# MCU.net
KiCad netlist of a schematic drawn in Altium Designer
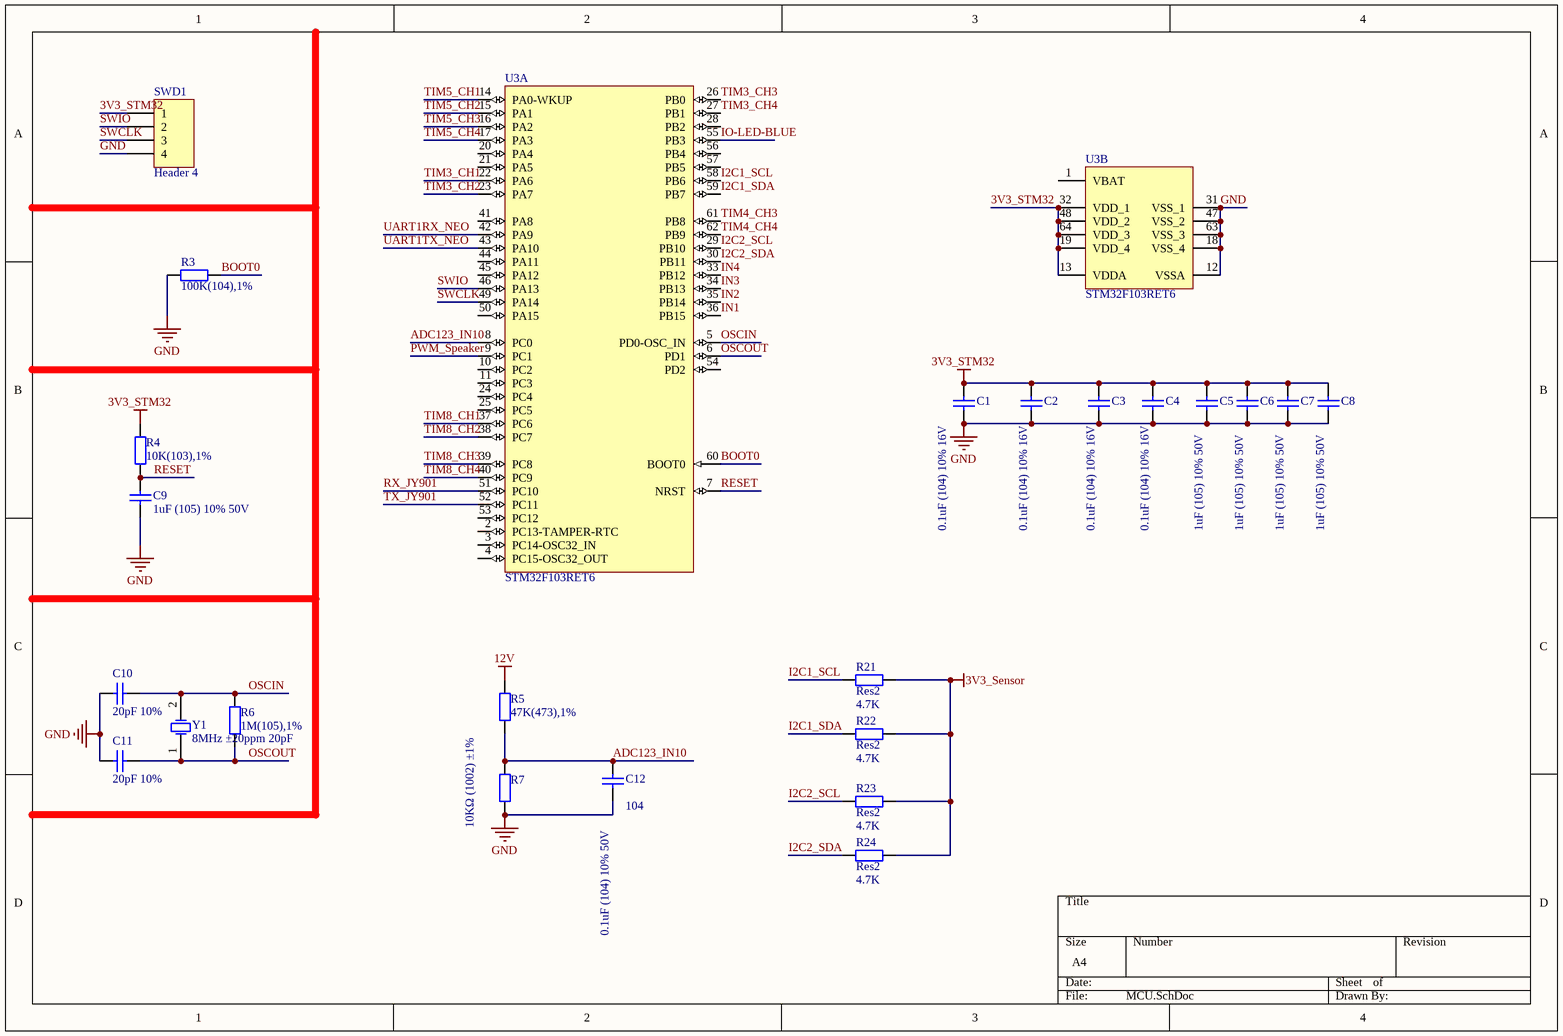
[diagram p0: MCU.SchDoc]

(export (version "E")
  (design (tool "Eeschema 10.0.6"))
  (components
    (comp (ref "C1")
      (value "0.1uF (104) 10% 16V")
      (footprint "0603_C")
      (description "Capacitor")
      (fields (field (name "PUBLISHER") "Altium Limited"))
      (libsource (lib "STM32F103C8T6(原理图库)") (part "Cap"))
    )
    (comp (ref "C2")
      (value "0.1uF (104) 10% 16V")
      (footprint "0603_C")
      (description "Capacitor")
      (fields (field (name "PUBLISHER") "Altium Limited"))
      (libsource (lib "STM32F103C8T6(原理图库)") (part "Cap"))
    )
    (comp (ref "C3")
      (value "0.1uF (104) 10% 16V")
      (footprint "0603_C")
      (description "Capacitor")
      (fields (field (name "PUBLISHER") "Altium Limited"))
      (libsource (lib "STM32F103C8T6(原理图库)") (part "Cap"))
    )
    (comp (ref "C4")
      (value "0.1uF (104) 10% 16V")
      (footprint "0603_C")
      (description "Capacitor")
      (fields (field (name "PUBLISHER") "Altium Limited"))
      (libsource (lib "STM32F103C8T6(原理图库)") (part "Cap"))
    )
    (comp (ref "C5")
      (value "1uF (105) 10% 50V")
      (footprint "0603_C")
      (description "贴片电容")
      (libsource (lib "Miscellaneous Devices LC") (part "0603 1uF (105) 10% 50V"))
    )
    (comp (ref "C6")
      (value "1uF (105) 10% 50V")
      (footprint "0603_C")
      (description "贴片电容")
      (libsource (lib "Miscellaneous Devices LC") (part "0603 1uF (105) 10% 50V"))
    )
    (comp (ref "C7")
      (value "1uF (105) 10% 50V")
      (footprint "0603_C")
      (description "贴片电容")
      (libsource (lib "Miscellaneous Devices LC") (part "0603 1uF (105) 10% 50V"))
    )
    (comp (ref "C8")
      (value "1uF (105) 10% 50V")
      (footprint "0603_C")
      (description "贴片电容")
      (libsource (lib "Miscellaneous Devices LC") (part "0603 1uF (105) 10% 50V"))
    )
    (comp (ref "C9")
      (value "1uF (105) 10% 50V")
      (footprint "0603_C")
      (description "Capacitor")
      (fields (field (name "PUBLISHER") "Altium Limited"))
      (libsource (lib "STM32F103C8T6(原理图库)") (part "Cap"))
    )
    (comp (ref "C10")
      (value "20pF 10%")
      (footprint "0603_C")
      (description "Capacitor")
      (fields (field (name "PUBLISHER") "Altium Limited"))
      (libsource (lib "STM32F103C8T6(原理图库)") (part "Cap"))
    )
    (comp (ref "C11")
      (value "20pF 10%")
      (footprint "0603_C")
      (description "Capacitor")
      (fields (field (name "PUBLISHER") "Altium Limited"))
      (libsource (lib "STM32F103C8T6(原理图库)") (part "Cap"))
    )
    (comp (ref "C12")
      (value "0.1uF (104) 10% 50V")
      (footprint "0603_C")
      (description "Capacitor")
      (fields (field (name "ALTIUM_VALUE") "104") (field (name "PUBLISHER") "Altium Limited"))
      (libsource (lib "Miscellaneous Devices") (part "Cap"))
    )
    (comp (ref "R3")
      (value "100K(104),1%")
      (footprint "0603_R")
      (description "Resistor")
      (fields (field (name "PUBLISHER") "Altium Limited"))
      (libsource (lib "") (part "Res2_1"))
    )
    (comp (ref "R4")
      (value "10K(103),1%")
      (footprint "0603_R")
      (description "Resistor")
      (fields (field (name "PUBLISHER") "Altium Limited"))
      (libsource (lib "STM32F103C8T6(原理图库)") (part "Res2"))
    )
    (comp (ref "R5")
      (value "47K(473),1%")
      (footprint "0603_R")
      (description "Resistor")
      (fields (field (name "PUBLISHER") "Altium Limited"))
      (libsource (lib "STM32F103C8T6(原理图库)") (part "Res2"))
    )
    (comp (ref "R6")
      (value "1M(105),1%")
      (footprint "0603_R")
      (description "Resistor")
      (fields (field (name "PUBLISHER") "Altium Limited"))
      (libsource (lib "STM32F103C8T6(原理图库)") (part "Res2"))
    )
    (comp (ref "R7")
      (value "10KΩ (1002) ±1%")
      (footprint "0603_R")
      (description "贴片电阻")
      (libsource (lib "Miscellaneous Devices LC") (part "0603 10KΩ (1002) 1%"))
    )
    (comp (ref "R21")
      (value "Res2")
      (footprint "R0603")
      (description "Resistor")
      (fields (field (name "ALTIUM_VALUE") "4.7K") (field (name "PUBLISHER") "Altium Limited"))
      (libsource (lib "Miscellaneous Devices") (part "Res2"))
    )
    (comp (ref "R22")
      (value "Res2")
      (footprint "R0603")
      (description "Resistor")
      (fields (field (name "ALTIUM_VALUE") "4.7K") (field (name "PUBLISHER") "Altium Limited"))
      (libsource (lib "Miscellaneous Devices") (part "Res2"))
    )
    (comp (ref "R23")
      (value "Res2")
      (footprint "R0603")
      (description "Resistor")
      (fields (field (name "ALTIUM_VALUE") "4.7K") (field (name "PUBLISHER") "Altium Limited"))
      (libsource (lib "Miscellaneous Devices") (part "Res2"))
    )
    (comp (ref "R24")
      (value "Res2")
      (footprint "R0603")
      (description "Resistor")
      (fields (field (name "ALTIUM_VALUE") "4.7K") (field (name "PUBLISHER") "Altium Limited"))
      (libsource (lib "Miscellaneous Devices") (part "Res2"))
    )
    (comp (ref "SWD1")
      (value "Header 4")
      (footprint "HDR1X4")
      (description "Header, 4-Pin")
      (fields (field (name "PUBLISHER") "Altium Limited"))
      (libsource (lib "Miscellaneous Connectors") (part "Header 4"))
    )
    (comp (ref "U3")
      (value "STM32F103RET6")
      (footprint "LQFP-64_10x10x05P")
      (description "ARM")
      (libsource (lib "Miscellaneous Devices LC") (part "STM32F103RET6"))
    )
    (comp (ref "Y1")
      (value "8MHz ±20ppm 20pF")
      (footprint "SMD-5032_2P")
      (description "贴片晶振")
      (libsource (lib "Miscellaneous Devices LC") (part "SMD-5032_2P 8MHz 20ppm 20pF"))
    )
  )
  (nets
    (net (code "1") (name "/ADC123_IN10") (class "Default")
      (node (ref "C12") (pin "2") (pinfunction "2_2") (pintype "passive"))
      (node (ref "R5") (pin "1") (pinfunction "1_1") (pintype "passive"))
      (node (ref "R7") (pin "2") (pinfunction "2_2") (pintype "passive"))
      (node (ref "U3") (pin "8") (pinfunction "PC0_8") (pintype "bidirectional"))
    )
    (net (code "2") (name "/BOOT0") (class "Default")
      (node (ref "R3") (pin "2") (pinfunction "2_2") (pintype "passive"))
      (node (ref "U3") (pin "60") (pinfunction "BOOT0_60") (pintype "input"))
    )
    (net (code "3") (name "/I2C1_SCL") (class "Default")
      (node (ref "R21") (pin "1") (pinfunction "1_1") (pintype "passive"))
      (node (ref "U3") (pin "58") (pinfunction "PB6_58") (pintype "bidirectional"))
    )
    (net (code "4") (name "/I2C1_SDA") (class "Default")
      (node (ref "R22") (pin "1") (pinfunction "1_1") (pintype "passive"))
      (node (ref "U3") (pin "59") (pinfunction "PB7_59") (pintype "bidirectional"))
    )
    (net (code "5") (name "/I2C2_SCL") (class "Default")
      (node (ref "R23") (pin "1") (pinfunction "1_1") (pintype "passive"))
      (node (ref "U3") (pin "29") (pinfunction "PB10_29") (pintype "bidirectional"))
    )
    (net (code "6") (name "/I2C2_SDA") (class "Default")
      (node (ref "R24") (pin "1") (pinfunction "1_1") (pintype "passive"))
      (node (ref "U3") (pin "30") (pinfunction "PB11_30") (pintype "bidirectional"))
    )
    (net (code "7") (name "/IN1") (class "Default")
      (node (ref "U3") (pin "36") (pinfunction "PB15_36") (pintype "bidirectional"))
    )
    (net (code "8") (name "/IN2") (class "Default")
      (node (ref "U3") (pin "35") (pinfunction "PB14_35") (pintype "bidirectional"))
    )
    (net (code "9") (name "/IN3") (class "Default")
      (node (ref "U3") (pin "34") (pinfunction "PB13_34") (pintype "bidirectional"))
    )
    (net (code "10") (name "/IN4") (class "Default")
      (node (ref "U3") (pin "33") (pinfunction "PB12_33") (pintype "bidirectional"))
    )
    (net (code "11") (name "/IO-LED-BLUE") (class "Default")
      (node (ref "U3") (pin "55") (pinfunction "PB3_55") (pintype "bidirectional"))
    )
    (net (code "12") (name "/OSCIN") (class "Default")
      (node (ref "C10") (pin "1") (pinfunction "1_1") (pintype "passive"))
      (node (ref "R6") (pin "2") (pinfunction "2_2") (pintype "passive"))
      (node (ref "U3") (pin "5") (pinfunction "PD0-OSC_IN_5") (pintype "bidirectional"))
      (node (ref "Y1") (pin "2") (pinfunction "OSC2_2") (pintype "passive"))
    )
    (net (code "13") (name "/OSCOUT") (class "Default")
      (node (ref "C11") (pin "1") (pinfunction "1_1") (pintype "passive"))
      (node (ref "R6") (pin "1") (pinfunction "1_1") (pintype "passive"))
      (node (ref "U3") (pin "6") (pinfunction "PD1_6") (pintype "bidirectional"))
      (node (ref "Y1") (pin "1") (pinfunction "OSC1_1") (pintype "passive"))
    )
    (net (code "14") (name "/PWM_Speaker") (class "Default")
      (node (ref "U3") (pin "9") (pinfunction "PC1_9") (pintype "bidirectional"))
    )
    (net (code "15") (name "/RESET") (class "Default")
      (node (ref "C9") (pin "2") (pinfunction "2_2") (pintype "passive"))
      (node (ref "R4") (pin "1") (pinfunction "1_1") (pintype "passive"))
      (node (ref "U3") (pin "7") (pinfunction "NRST_7") (pintype "bidirectional"))
    )
    (net (code "16") (name "/RX_JY901") (class "Default")
      (node (ref "U3") (pin "51") (pinfunction "PC10_51") (pintype "bidirectional"))
    )
    (net (code "17") (name "/SWCLK") (class "Default")
      (node (ref "SWD1") (pin "3") (pinfunction "3_3") (pintype "passive"))
      (node (ref "U3") (pin "49") (pinfunction "PA14_49") (pintype "bidirectional"))
    )
    (net (code "18") (name "/SWIO") (class "Default")
      (node (ref "SWD1") (pin "2") (pinfunction "2_2") (pintype "passive"))
      (node (ref "U3") (pin "46") (pinfunction "PA13_46") (pintype "bidirectional"))
    )
    (net (code "19") (name "/TIM3_CH1") (class "Default")
      (node (ref "U3") (pin "22") (pinfunction "PA6_22") (pintype "bidirectional"))
    )
    (net (code "20") (name "/TIM3_CH2") (class "Default")
      (node (ref "U3") (pin "23") (pinfunction "PA7_23") (pintype "bidirectional"))
    )
    (net (code "21") (name "/TIM3_CH3") (class "Default")
      (node (ref "U3") (pin "26") (pinfunction "PB0_26") (pintype "bidirectional"))
    )
    (net (code "22") (name "/TIM3_CH4") (class "Default")
      (node (ref "U3") (pin "27") (pinfunction "PB1_27") (pintype "bidirectional"))
    )
    (net (code "23") (name "/TIM4_CH3") (class "Default")
      (node (ref "U3") (pin "61") (pinfunction "PB8_61") (pintype "bidirectional"))
    )
    (net (code "24") (name "/TIM4_CH4") (class "Default")
      (node (ref "U3") (pin "62") (pinfunction "PB9_62") (pintype "bidirectional"))
    )
    (net (code "25") (name "/TIM5_CH1") (class "Default")
      (node (ref "U3") (pin "14") (pinfunction "PA0-WKUP_14") (pintype "bidirectional"))
    )
    (net (code "26") (name "/TIM5_CH2") (class "Default")
      (node (ref "U3") (pin "15") (pinfunction "PA1_15") (pintype "bidirectional"))
    )
    (net (code "27") (name "/TIM5_CH3") (class "Default")
      (node (ref "U3") (pin "16") (pinfunction "PA2_16") (pintype "bidirectional"))
    )
    (net (code "28") (name "/TIM5_CH4") (class "Default")
      (node (ref "U3") (pin "17") (pinfunction "PA3_17") (pintype "bidirectional"))
    )
    (net (code "29") (name "/TIM8_CH1") (class "Default")
      (node (ref "U3") (pin "37") (pinfunction "PC6_37") (pintype "bidirectional"))
    )
    (net (code "30") (name "/TIM8_CH2") (class "Default")
      (node (ref "U3") (pin "38") (pinfunction "PC7_38") (pintype "bidirectional"))
    )
    (net (code "31") (name "/TIM8_CH3") (class "Default")
      (node (ref "U3") (pin "39") (pinfunction "PC8_39") (pintype "bidirectional"))
    )
    (net (code "32") (name "/TIM8_CH4") (class "Default")
      (node (ref "U3") (pin "40") (pinfunction "PC9_40") (pintype "bidirectional"))
    )
    (net (code "33") (name "/TX_JY901") (class "Default")
      (node (ref "U3") (pin "52") (pinfunction "PC11_52") (pintype "bidirectional"))
    )
    (net (code "34") (name "/UART1RX_NEO") (class "Default")
      (node (ref "U3") (pin "42") (pinfunction "PA9_42") (pintype "bidirectional"))
    )
    (net (code "35") (name "/UART1TX_NEO") (class "Default")
      (node (ref "U3") (pin "43") (pinfunction "PA10_43") (pintype "bidirectional"))
    )
    (net (code "36") (name "3V3_STM32") (class "Default")
      (node (ref "C1") (pin "2") (pinfunction "2_2") (pintype "passive"))
      (node (ref "C2") (pin "2") (pinfunction "2_2") (pintype "passive"))
      (node (ref "C3") (pin "2") (pinfunction "2_2") (pintype "passive"))
      (node (ref "C4") (pin "2") (pinfunction "2_2") (pintype "passive"))
      (node (ref "C5") (pin "2") (pinfunction "2_2") (pintype "passive"))
      (node (ref "C6") (pin "2") (pinfunction "2_2") (pintype "passive"))
      (node (ref "C7") (pin "2") (pinfunction "2_2") (pintype "passive"))
      (node (ref "C8") (pin "2") (pinfunction "2_2") (pintype "passive"))
      (node (ref "R4") (pin "2") (pinfunction "2_2") (pintype "passive"))
      (node (ref "SWD1") (pin "1") (pinfunction "1_1") (pintype "passive"))
      (node (ref "U3") (pin "13") (pinfunction "VDDA_13") (pintype "power_in"))
      (node (ref "U3") (pin "19") (pinfunction "VDD_4_19") (pintype "power_in"))
      (node (ref "U3") (pin "32") (pinfunction "VDD_1_32") (pintype "power_in"))
      (node (ref "U3") (pin "48") (pinfunction "VDD_2_48") (pintype "power_in"))
      (node (ref "U3") (pin "64") (pinfunction "VDD_3_64") (pintype "power_in"))
    )
    (net (code "37") (name "3V3_Sensor") (class "Default")
      (node (ref "R21") (pin "2") (pinfunction "2_2") (pintype "passive"))
      (node (ref "R22") (pin "2") (pinfunction "2_2") (pintype "passive"))
      (node (ref "R23") (pin "2") (pinfunction "2_2") (pintype "passive"))
      (node (ref "R24") (pin "2") (pinfunction "2_2") (pintype "passive"))
    )
    (net (code "38") (name "12V") (class "Default")
      (node (ref "R5") (pin "2") (pinfunction "2_2") (pintype "passive"))
    )
    (net (code "39") (name "GND") (class "Default")
      (node (ref "C1") (pin "1") (pinfunction "1_1") (pintype "passive"))
      (node (ref "C10") (pin "2") (pinfunction "2_2") (pintype "passive"))
      (node (ref "C11") (pin "2") (pinfunction "2_2") (pintype "passive"))
      (node (ref "C12") (pin "1") (pinfunction "1_1") (pintype "passive"))
      (node (ref "C2") (pin "1") (pinfunction "1_1") (pintype "passive"))
      (node (ref "C3") (pin "1") (pinfunction "1_1") (pintype "passive"))
      (node (ref "C4") (pin "1") (pinfunction "1_1") (pintype "passive"))
      (node (ref "C5") (pin "1") (pinfunction "1_1") (pintype "passive"))
      (node (ref "C6") (pin "1") (pinfunction "1_1") (pintype "passive"))
      (node (ref "C7") (pin "1") (pinfunction "1_1") (pintype "passive"))
      (node (ref "C8") (pin "1") (pinfunction "1_1") (pintype "passive"))
      (node (ref "C9") (pin "1") (pinfunction "1_1") (pintype "passive"))
      (node (ref "R3") (pin "1") (pinfunction "1_1") (pintype "passive"))
      (node (ref "R7") (pin "1") (pinfunction "1_1") (pintype "passive"))
      (node (ref "SWD1") (pin "4") (pinfunction "4_4") (pintype "passive"))
      (node (ref "U3") (pin "12") (pinfunction "VSSA_12") (pintype "power_in"))
      (node (ref "U3") (pin "18") (pinfunction "VSS_4_18") (pintype "power_in"))
      (node (ref "U3") (pin "31") (pinfunction "VSS_1_31") (pintype "power_in"))
      (node (ref "U3") (pin "47") (pinfunction "VSS_2_47") (pintype "power_in"))
      (node (ref "U3") (pin "63") (pinfunction "VSS_3_63") (pintype "power_in"))
    )
    (net (code "40") (name "unconnected-(U3A-PA4-Pad20)") (class "Default")
      (node (ref "U3") (pin "20") (pinfunction "PA4_20") (pintype "bidirectional"))
    )
    (net (code "41") (name "unconnected-(U3A-PA5-Pad21)") (class "Default")
      (node (ref "U3") (pin "21") (pinfunction "PA5_21") (pintype "bidirectional"))
    )
    (net (code "42") (name "unconnected-(U3A-PA8-Pad41)") (class "Default")
      (node (ref "U3") (pin "41") (pinfunction "PA8_41") (pintype "bidirectional"))
    )
    (net (code "43") (name "unconnected-(U3A-PA11-Pad44)") (class "Default")
      (node (ref "U3") (pin "44") (pinfunction "PA11_44") (pintype "bidirectional"))
    )
    (net (code "44") (name "unconnected-(U3A-PA12-Pad45)") (class "Default")
      (node (ref "U3") (pin "45") (pinfunction "PA12_45") (pintype "bidirectional"))
    )
    (net (code "45") (name "unconnected-(U3A-PA15-Pad50)") (class "Default")
      (node (ref "U3") (pin "50") (pinfunction "PA15_50") (pintype "bidirectional"))
    )
    (net (code "46") (name "unconnected-(U3A-PB2-Pad28)") (class "Default")
      (node (ref "U3") (pin "28") (pinfunction "PB2_28") (pintype "bidirectional"))
    )
    (net (code "47") (name "unconnected-(U3A-PB4-Pad56)") (class "Default")
      (node (ref "U3") (pin "56") (pinfunction "PB4_56") (pintype "bidirectional"))
    )
    (net (code "48") (name "unconnected-(U3A-PB5-Pad57)") (class "Default")
      (node (ref "U3") (pin "57") (pinfunction "PB5_57") (pintype "bidirectional"))
    )
    (net (code "49") (name "unconnected-(U3A-PC2-Pad10)") (class "Default")
      (node (ref "U3") (pin "10") (pinfunction "PC2_10") (pintype "bidirectional"))
    )
    (net (code "50") (name "unconnected-(U3A-PC3-Pad11)") (class "Default")
      (node (ref "U3") (pin "11") (pinfunction "PC3_11") (pintype "bidirectional"))
    )
    (net (code "51") (name "unconnected-(U3A-PC4-Pad24)") (class "Default")
      (node (ref "U3") (pin "24") (pinfunction "PC4_24") (pintype "bidirectional"))
    )
    (net (code "52") (name "unconnected-(U3A-PC5-Pad25)") (class "Default")
      (node (ref "U3") (pin "25") (pinfunction "PC5_25") (pintype "bidirectional"))
    )
    (net (code "53") (name "unconnected-(U3A-PC12-Pad53)") (class "Default")
      (node (ref "U3") (pin "53") (pinfunction "PC12_53") (pintype "bidirectional"))
    )
    (net (code "54") (name "unconnected-(U3A-PC13-TAMPER-RTC-Pad2)") (class "Default")
      (node (ref "U3") (pin "2") (pinfunction "PC13-TAMPER-RTC_2") (pintype "bidirectional"))
    )
    (net (code "55") (name "unconnected-(U3A-PC14-OSC32_IN-Pad3)") (class "Default")
      (node (ref "U3") (pin "3") (pinfunction "PC14-OSC32_IN_3") (pintype "bidirectional"))
    )
    (net (code "56") (name "unconnected-(U3A-PC15-OSC32_OUT-Pad4)") (class "Default")
      (node (ref "U3") (pin "4") (pinfunction "PC15-OSC32_OUT_4") (pintype "bidirectional"))
    )
    (net (code "57") (name "unconnected-(U3A-PD2-Pad54)") (class "Default")
      (node (ref "U3") (pin "54") (pinfunction "PD2_54") (pintype "bidirectional"))
    )
    (net (code "58") (name "unconnected-(U3B-VBAT-Pad1)") (class "Default")
      (node (ref "U3") (pin "1") (pinfunction "VBAT_1") (pintype "power_in"))
    )
  )
)
